# Uno_Hat.net
KiCad netlist of a schematic drawn in EasyEDA
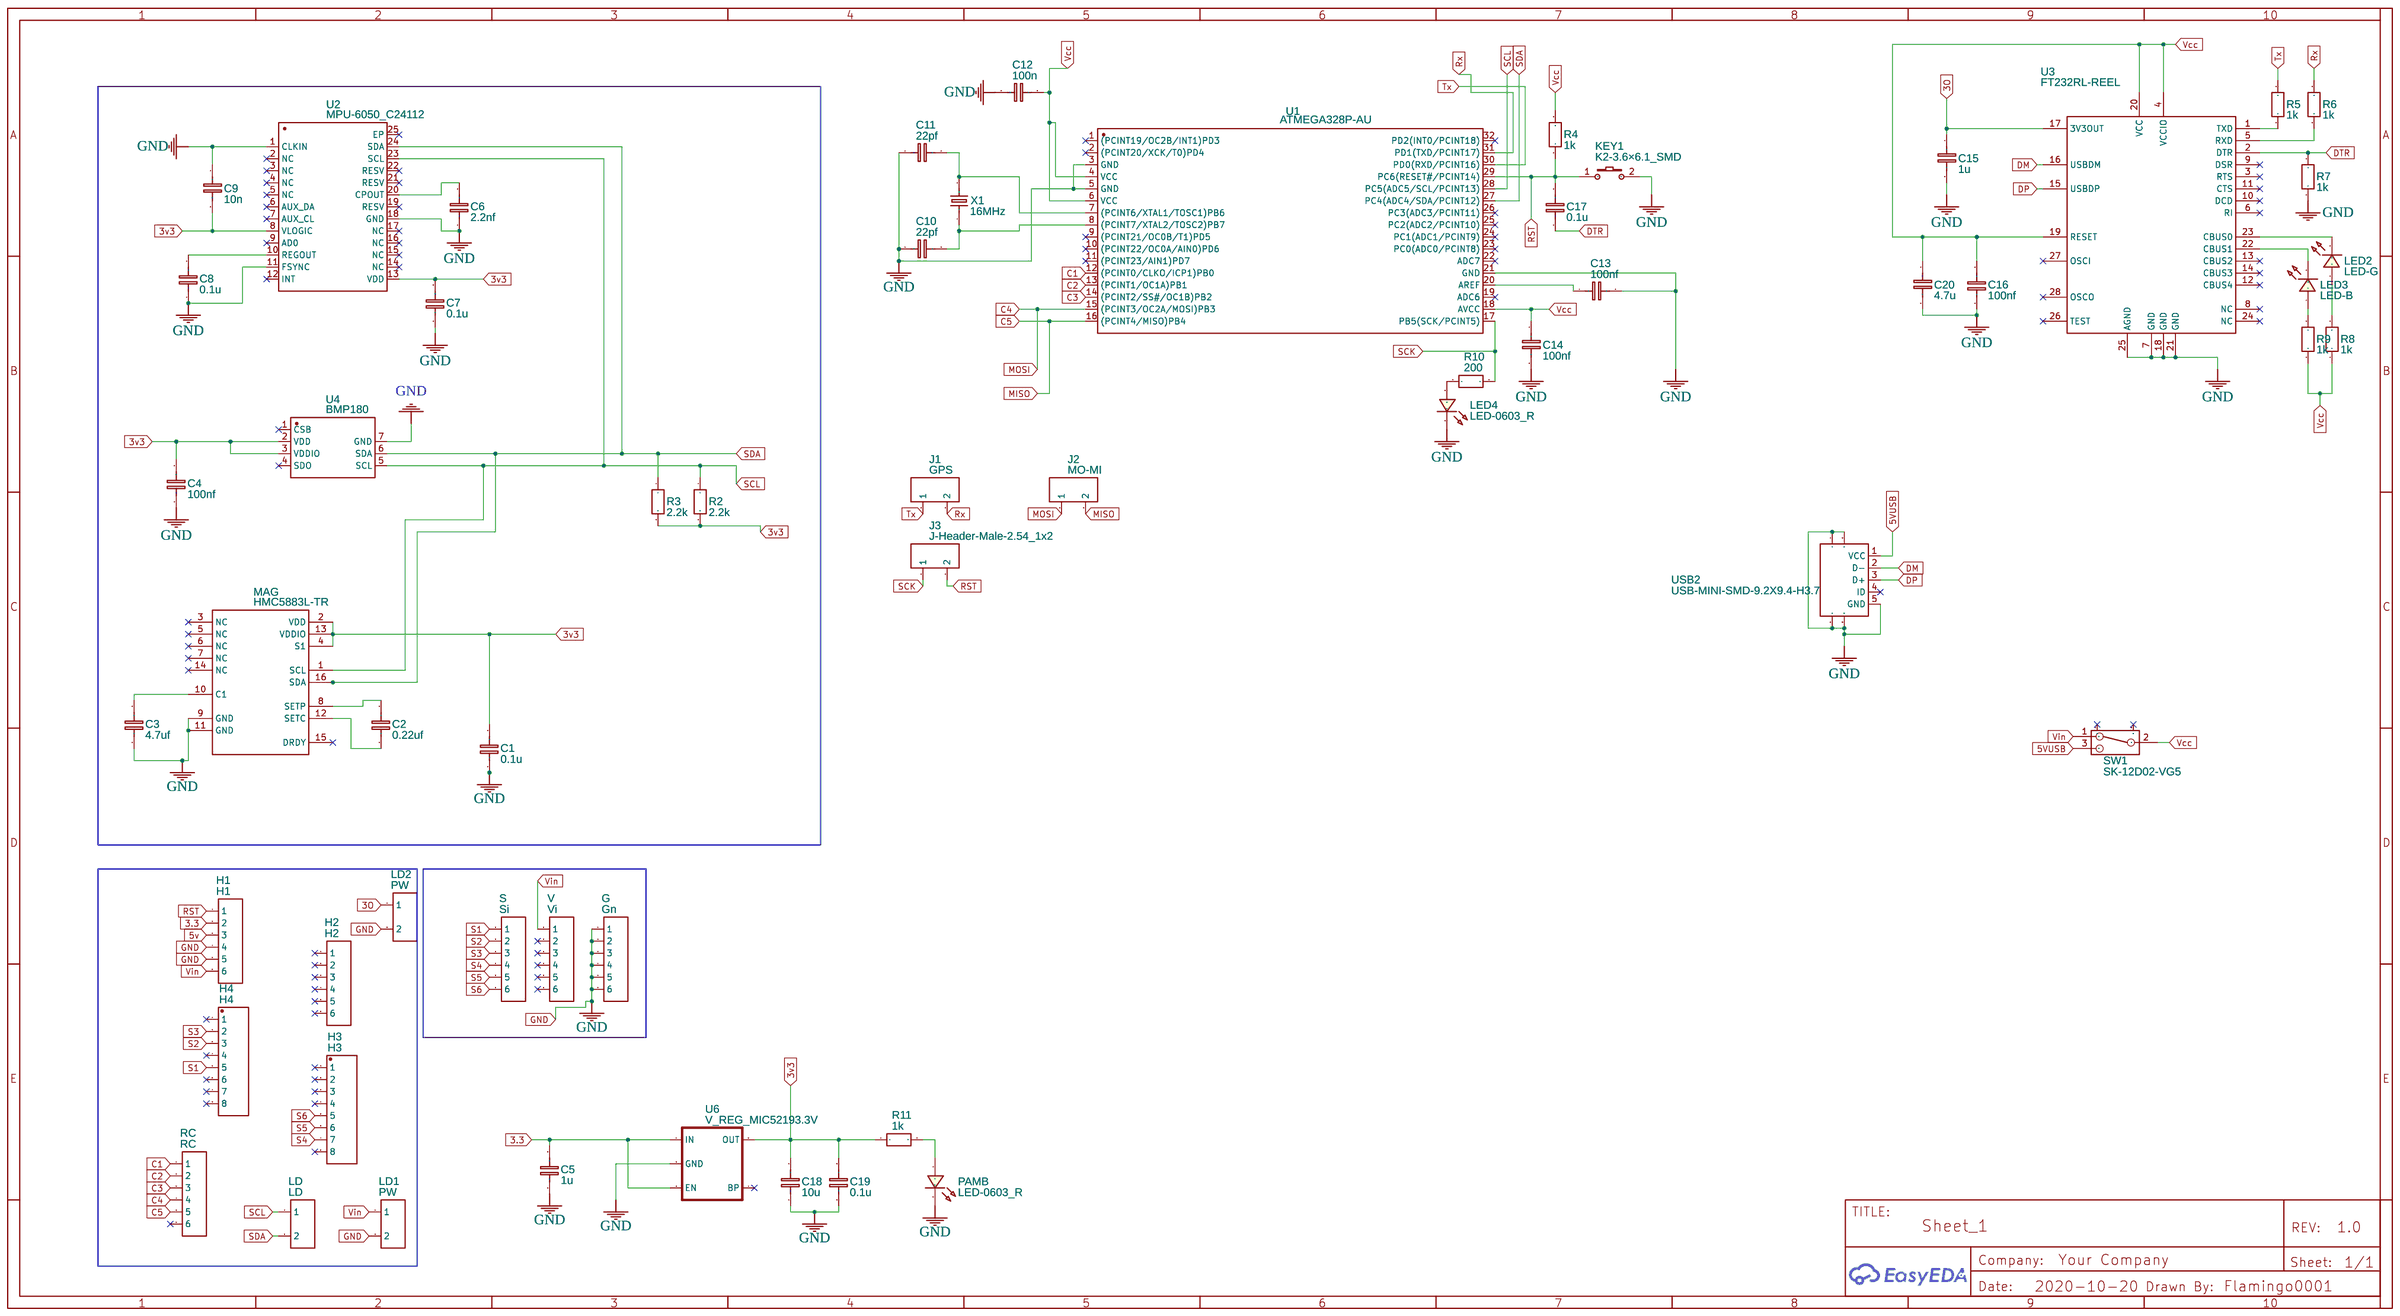
[diagram p0: schematic sheet]

(export (version "E")
  (design (tool "Eeschema 10.0.6"))
  (components
    (comp (ref "C1") (value "0.1u") (libsource (lib "") (part "C_0603_EU_3")))
    (comp (ref "C2") (value "0.22uf") (libsource (lib "") (part "C_0603_EU_3")))
    (comp (ref "C3") (value "4.7uf") (libsource (lib "") (part "C_0603_EU_4")))
    (comp (ref "C4") (value "100nf") (libsource (lib "") (part "C_0603_EU_4")))
    (comp (ref "C5") (value "1u") (libsource (lib "") (part "C_0603_EU_2")))
    (comp (ref "C6") (value "2.2nf") (libsource (lib "") (part "C_0603_EU_2")))
    (comp (ref "C7") (value "0.1u") (libsource (lib "") (part "C_0603_EU_2")))
    (comp (ref "C8") (value "0.1u") (libsource (lib "") (part "C_0603_EU")))
    (comp (ref "C9") (value "10n") (libsource (lib "") (part "C_0603_EU_1")))
    (comp (ref "C10") (value "22pf") (libsource (lib "") (part "C_0603_EU_5")))
    (comp (ref "C11") (value "22pf") (libsource (lib "") (part "C_0603_EU_5")))
    (comp (ref "C12") (value "100n") (libsource (lib "") (part "C_0603_EU_5")))
    (comp (ref "C13") (value "100nf") (libsource (lib "") (part "C_0603_EU_5")))
    (comp (ref "C14") (value "100nf") (libsource (lib "") (part "C_0603_EU_1")))
    (comp (ref "C15") (value "1u") (libsource (lib "") (part "C_0603_EU_1")))
    (comp (ref "C16") (value "100nf") (libsource (lib "") (part "C_0603_EU")))
    (comp (ref "C17") (value "0.1u") (libsource (lib "") (part "C_0603_EU")))
    (comp (ref "C18") (value "10u") (libsource (lib "") (part "C_0603_EU")))
    (comp (ref "C19") (value "0.1u") (libsource (lib "") (part "C_0603_EU")))
    (comp (ref "C20") (value "4.7u") (libsource (lib "") (part "C_0603_EU_1")))
    (comp (ref "G")
      (value "Gn")
      (fields
        (field (name "BOM_Manufacturer Part") "Header-Male-2.54_1x6")
        (field (name "BOM_Supplier Part") "C37208")
      )
      (libsource (lib "") (part "Header-Male-2.54_1x6_3"))
    )
    (comp (ref "H1")
      (value "H1")
      (fields
        (field (name "BOM_Manufacturer Part") "Header-Male-2.54_1x6")
        (field (name "BOM_Supplier Part") "C37208")
      )
      (libsource (lib "") (part "Header-Male-2.54_1x6_1"))
    )
    (comp (ref "H2")
      (value "H2")
      (fields
        (field (name "BOM_Manufacturer Part") "Header-Male-2.54_1x6")
        (field (name "BOM_Supplier Part") "C37208")
      )
      (libsource (lib "") (part "Header-Male-2.54_1x6_1"))
    )
    (comp (ref "H3")
      (value "H3")
      (fields
        (field (name "BOM_Manufacturer Part") "210S-1*8P L=11.6MMGold-plated black")
        (field (name "BOM_Supplier Part") "C124381")
      )
      (libsource (lib "") (part "Header-Male-2.54_1x8"))
    )
    (comp (ref "H4")
      (value "H4")
      (fields
        (field (name "BOM_Manufacturer Part") "210S-1*8P L=11.6MMGold-plated black")
        (field (name "BOM_Supplier Part") "C124381")
      )
      (libsource (lib "") (part "Header-Male-2.54_1x8"))
    )
    (comp (ref "J1")
      (value "GPS")
      (fields (field (name "BOM_Manufacturer Part") "826629-2") (field (name "BOM_Supplier Part") "C86471"))
      (libsource (lib "") (part "J-Header-Male-2.54_1x2"))
    )
    (comp (ref "J2")
      (value "MO-MI")
      (fields (field (name "BOM_Manufacturer Part") "826629-2") (field (name "BOM_Supplier Part") "C86471"))
      (libsource (lib "") (part "J-Header-Male-2.54_1x2"))
    )
    (comp (ref "J3")
      (value "J-Header-Male-2.54_1x2")
      (fields (field (name "BOM_Manufacturer Part") "826629-2") (field (name "BOM_Supplier Part") "C86471"))
      (libsource (lib "") (part "J-Header-Male-2.54_1x2"))
    )
    (comp (ref "KEY1")
      (value "K2-3.6×6.1_SMD")
      (fields
        (field (name "BOM_Manufacturer Part") "K2-1107ST-A4SW-06")
        (field (name "BOM_Supplier Part") "C118141")
      )
      (libsource (lib "") (part "K2-3.6×6.1_SMD"))
    )
    (comp (ref "LD")
      (value "LD")
      (fields (field (name "BOM_Manufacturer Part") "826629-2") (field (name "BOM_Supplier Part") "C86471"))
      (libsource (lib "") (part "Header-Male-2.54_1x2"))
    )
    (comp (ref "LD1")
      (value "PW")
      (fields (field (name "BOM_Manufacturer Part") "826629-2") (field (name "BOM_Supplier Part") "C86471"))
      (libsource (lib "") (part "Header-Male-2.54_1x2"))
    )
    (comp (ref "LD2")
      (value "PW")
      (fields (field (name "BOM_Manufacturer Part") "826629-2") (field (name "BOM_Supplier Part") "C86471"))
      (libsource (lib "") (part "Header-Male-2.54_1x2"))
    )
    (comp (ref "LED2")
      (value "LED-G")
      (fields
        (field (name "BOM_Manufacturer Part") "19-217/GHC-YR1S2/3T")
        (field (name "BOM_Supplier Part") "C72043")
      )
      (libsource (lib "") (part "LED-0603_G"))
    )
    (comp (ref "LED3")
      (value "LED-B")
      (fields
        (field (name "BOM_Manufacturer Part") "19-217/BHC-ZL1M2RY/3T")
        (field (name "BOM_Supplier Part") "C72041")
      )
      (libsource (lib "") (part "LED-0603_B"))
    )
    (comp (ref "LED4")
      (value "LED-0603_R")
      (fields
        (field (name "BOM_Manufacturer Part") "19-217/R6C-AL1M2VY/3T")
        (field (name "BOM_Supplier Part") "C72044")
      )
      (libsource (lib "") (part "LED-0603_R_1"))
    )
    (comp (ref "MAG")
      (value "HMC5883L-TR")
      (fields (field (name "BOM_Supplier Part") "C15640"))
      (libsource (lib "") (part "HMC5883L-TR"))
    )
    (comp (ref "PAMB")
      (value "LED-0603_R")
      (fields
        (field (name "BOM_Manufacturer Part") "19-217/R6C-AL1M2VY/3T")
        (field (name "BOM_Supplier Part") "C72044")
      )
      (libsource (lib "") (part "LED-0603_R"))
    )
    (comp (ref "R2") (value "2.2k") (libsource (lib "") (part "R_0603_EU_2")))
    (comp (ref "R3") (value "2.2k") (libsource (lib "") (part "R_0603_EU_2")))
    (comp (ref "R4") (value "1k") (libsource (lib "") (part "R_0603_EU_1")))
    (comp (ref "R5") (value "1k") (libsource (lib "") (part "R_0603_EU_1")))
    (comp (ref "R6") (value "1k") (libsource (lib "") (part "R_0603_EU_1")))
    (comp (ref "R7") (value "1k") (libsource (lib "") (part "R_0603_EU_1")))
    (comp (ref "R8") (value "1k") (libsource (lib "") (part "R_0603_EU_1")))
    (comp (ref "R9") (value "1k") (libsource (lib "") (part "R_0603_EU_1")))
    (comp (ref "R10") (value "200") (libsource (lib "") (part "R_0603_EU")))
    (comp (ref "R11") (value "1k") (libsource (lib "") (part "R_0603_EU")))
    (comp (ref "RC")
      (value "RC")
      (fields
        (field (name "BOM_Manufacturer Part") "Header-Male-2.54_1x6")
        (field (name "BOM_Supplier Part") "C37208")
      )
      (libsource (lib "") (part "Header-Male-2.54_1x6_4"))
    )
    (comp (ref "S")
      (value "Si")
      (fields
        (field (name "BOM_Manufacturer Part") "Header-Male-2.54_1x6")
        (field (name "BOM_Supplier Part") "C37208")
      )
      (libsource (lib "") (part "Header-Male-2.54_1x6_2"))
    )
    (comp (ref "SW1")
      (value "SK-12D02-VG5")
      (fields (field (name "BOM_Supplier Part") "C136722"))
      (libsource (lib "") (part "SK-12D02-VG5"))
    )
    (comp (ref "U1")
      (value "ATMEGA328P-AU")
      (fields (field (name "BOM_Supplier Part") "C14877"))
      (libsource (lib "") (part "ATMEGA328P-AU"))
    )
    (comp (ref "U2")
      (value "MPU-6050_C24112")
      (fields (field (name "BOM_Manufacturer Part") "MPU-6050") (field (name "BOM_Supplier Part") "C24112"))
      (libsource (lib "") (part "MPU-6050_C24112"))
    )
    (comp (ref "U3")
      (value "FT232RL-REEL")
      (fields (field (name "BOM_Supplier Part") "C8690"))
      (libsource (lib "") (part "FT232RL-REEL"))
    )
    (comp (ref "U4")
      (value "BMP180")
      (fields (field (name "BOM_Supplier Part") "C438474"))
      (libsource (lib "") (part "BMP180"))
    )
    (comp (ref "U6") (value "V_REG_MIC52193.3V") (libsource (lib "") (part "V_REG_MIC52193.3V")))
    (comp (ref "USB2")
      (value "USB-MINI-SMD-9.2X9.4-H3.7")
      (fields (field (name "BOM_Supplier Part") "C105424"))
      (libsource (lib "") (part "USB-MINI-SMD-9.2X9.4-H3.7"))
    )
    (comp (ref "V")
      (value "Vi")
      (fields
        (field (name "BOM_Manufacturer Part") "Header-Male-2.54_1x6")
        (field (name "BOM_Supplier Part") "C37208")
      )
      (libsource (lib "") (part "Header-Male-2.54_1x6"))
    )
    (comp (ref "X1")
      (value "16MHz")
      (fields
        (field (name "BOM_Manufacturer Part") "XIHCELNANF-16MHZ")
        (field (name "BOM_Supplier Part") "C295075")
      )
      (libsource (lib "") (part "XIHCELNANF-16MHZ"))
    )
  )
  (nets
    (net (code "1") (name "3.3") (class "Default")
      (node (ref "C5") (pin "2") (pinfunction "2_2") (pintype "unspecified"))
      (node (ref "H1") (pin "2") (pinfunction "2_2") (pintype "input"))
      (node (ref "U6") (pin "1") (pinfunction "IN_1") (pintype "input"))
      (node (ref "U6") (pin "3") (pinfunction "EN_3") (pintype "input"))
    )
    (net (code "2") (name "3O") (class "Default")
      (node (ref "C15") (pin "1") (pinfunction "1_1") (pintype "unspecified"))
      (node (ref "LD2") (pin "1") (pinfunction "1_1") (pintype "unspecified"))
      (node (ref "U3") (pin "17") (pinfunction "3V3OUT_17") (pintype "output"))
    )
    (net (code "3") (name "3v3") (class "Default")
      (node (ref "C1") (pin "2") (pinfunction "2_2") (pintype "unspecified"))
      (node (ref "C18") (pin "2") (pinfunction "2_2") (pintype "unspecified"))
      (node (ref "C19") (pin "2") (pinfunction "2_2") (pintype "unspecified"))
      (node (ref "C4") (pin "2") (pinfunction "2_2") (pintype "unspecified"))
      (node (ref "C7") (pin "2") (pinfunction "2_2") (pintype "unspecified"))
      (node (ref "C9") (pin "2") (pinfunction "2_2") (pintype "unspecified"))
      (node (ref "MAG") (pin "13") (pinfunction "VDDIO_13") (pintype "unspecified"))
      (node (ref "MAG") (pin "2") (pinfunction "VDD_2") (pintype "unspecified"))
      (node (ref "MAG") (pin "4") (pinfunction "S1_4") (pintype "unspecified"))
      (node (ref "R11") (pin "1") (pinfunction "1_1") (pintype "unspecified"))
      (node (ref "R2") (pin "2") (pinfunction "2_2") (pintype "unspecified"))
      (node (ref "R3") (pin "2") (pinfunction "2_2") (pintype "unspecified"))
      (node (ref "U2") (pin "13") (pinfunction "VDD_13") (pintype "unspecified"))
      (node (ref "U2") (pin "8") (pinfunction "VLOGIC_8") (pintype "unspecified"))
      (node (ref "U4") (pin "2") (pinfunction "VDD_2") (pintype "unspecified"))
      (node (ref "U4") (pin "3") (pinfunction "VDDIO_3") (pintype "unspecified"))
      (node (ref "U6") (pin "5") (pinfunction "OUT_5") (pintype "unspecified"))
    )
    (net (code "4") (name "5VUSB") (class "Default")
      (node (ref "SW1") (pin "3") (pinfunction "3_3") (pintype "unspecified"))
      (node (ref "USB2") (pin "1") (pinfunction "VCC_1") (pintype "input"))
    )
    (net (code "5") (name "5v") (class "Default")
      (node (ref "H1") (pin "3") (pinfunction "3_3") (pintype "input"))
    )
    (net (code "6") (name "C1") (class "Default")
      (node (ref "RC") (pin "1") (pinfunction "1_1") (pintype "input"))
      (node (ref "U1") (pin "12") (pinfunction "(PCINT0/CLKO/ICP1)PB0_12") (pintype "unspecified"))
    )
    (net (code "7") (name "C2") (class "Default")
      (node (ref "RC") (pin "2") (pinfunction "2_2") (pintype "input"))
      (node (ref "U1") (pin "13") (pinfunction "(PCINT1/OC1A)PB1_13") (pintype "unspecified"))
    )
    (net (code "8") (name "C3") (class "Default")
      (node (ref "RC") (pin "3") (pinfunction "3_3") (pintype "input"))
      (node (ref "U1") (pin "14") (pinfunction "(PCINT2/SS#/OC1B)PB2_14") (pintype "unspecified"))
    )
    (net (code "9") (name "C4") (class "Default")
      (node (ref "J2") (pin "1") (pinfunction "1_1") (pintype "unspecified"))
      (node (ref "RC") (pin "4") (pinfunction "4_4") (pintype "input"))
      (node (ref "U1") (pin "15") (pinfunction "(PCINT3/OC2A/MOSI)PB3_15") (pintype "unspecified"))
    )
    (net (code "10") (name "C5") (class "Default")
      (node (ref "J2") (pin "2") (pinfunction "2_2") (pintype "unspecified"))
      (node (ref "RC") (pin "5") (pinfunction "5_5") (pintype "input"))
      (node (ref "U1") (pin "16") (pinfunction "(PCINT4/MISO)PB4_16") (pintype "unspecified"))
    )
    (net (code "11") (name "DM") (class "Default")
      (node (ref "U3") (pin "16") (pinfunction "USBDM_16") (pintype "bidirectional"))
      (node (ref "USB2") (pin "2") (pinfunction "D-_2") (pintype "input"))
    )
    (net (code "12") (name "DP") (class "Default")
      (node (ref "U3") (pin "15") (pinfunction "USBDP_15") (pintype "bidirectional"))
      (node (ref "USB2") (pin "3") (pinfunction "D+_3") (pintype "input"))
    )
    (net (code "13") (name "DTR") (class "Default")
      (node (ref "C17") (pin "1") (pinfunction "1_1") (pintype "unspecified"))
      (node (ref "R7") (pin "2") (pinfunction "2_2") (pintype "unspecified"))
      (node (ref "U3") (pin "2") (pinfunction "DTR_2") (pintype "output"))
    )
    (net (code "14") (name "GND") (class "Default")
      (node (ref "C1") (pin "1") (pinfunction "1_1") (pintype "unspecified"))
      (node (ref "C10") (pin "1") (pinfunction "1_1") (pintype "unspecified"))
      (node (ref "C11") (pin "1") (pinfunction "1_1") (pintype "unspecified"))
      (node (ref "C12") (pin "1") (pinfunction "1_1") (pintype "unspecified"))
      (node (ref "C13") (pin "2") (pinfunction "2_2") (pintype "unspecified"))
      (node (ref "C14") (pin "2") (pinfunction "2_2") (pintype "unspecified"))
      (node (ref "C15") (pin "2") (pinfunction "2_2") (pintype "unspecified"))
      (node (ref "C16") (pin "1") (pinfunction "1_1") (pintype "unspecified"))
      (node (ref "C18") (pin "1") (pinfunction "1_1") (pintype "unspecified"))
      (node (ref "C19") (pin "1") (pinfunction "1_1") (pintype "unspecified"))
      (node (ref "C20") (pin "2") (pinfunction "2_2") (pintype "unspecified"))
      (node (ref "C3") (pin "1") (pinfunction "1_1") (pintype "unspecified"))
      (node (ref "C4") (pin "1") (pinfunction "1_1") (pintype "unspecified"))
      (node (ref "C5") (pin "1") (pinfunction "1_1") (pintype "unspecified"))
      (node (ref "C6") (pin "1") (pinfunction "1_1") (pintype "unspecified"))
      (node (ref "C7") (pin "1") (pinfunction "1_1") (pintype "unspecified"))
      (node (ref "C8") (pin "1") (pinfunction "1_1") (pintype "unspecified"))
      (node (ref "C9") (pin "1") (pinfunction "1_1") (pintype "unspecified"))
      (node (ref "G") (pin "1") (pinfunction "1_1") (pintype "input"))
      (node (ref "G") (pin "2") (pinfunction "2_2") (pintype "input"))
      (node (ref "G") (pin "3") (pinfunction "3_3") (pintype "input"))
      (node (ref "G") (pin "4") (pinfunction "4_4") (pintype "input"))
      (node (ref "G") (pin "5") (pinfunction "5_5") (pintype "input"))
      (node (ref "G") (pin "6") (pinfunction "6_6") (pintype "input"))
      (node (ref "H1") (pin "4") (pinfunction "4_4") (pintype "input"))
      (node (ref "H1") (pin "5") (pinfunction "5_5") (pintype "input"))
      (node (ref "KEY1") (pin "2") (pinfunction "2_2") (pintype "unspecified"))
      (node (ref "LD1") (pin "2") (pinfunction "2_2") (pintype "unspecified"))
      (node (ref "LD2") (pin "2") (pinfunction "2_2") (pintype "unspecified"))
      (node (ref "LED4") (pin "2") (pinfunction "2_2") (pintype "unspecified"))
      (node (ref "MAG") (pin "11") (pinfunction "GND_11") (pintype "unspecified"))
      (node (ref "MAG") (pin "9") (pinfunction "GND_9") (pintype "unspecified"))
      (node (ref "PAMB") (pin "2") (pinfunction "2_2") (pintype "unspecified"))
      (node (ref "R7") (pin "1") (pinfunction "1_1") (pintype "unspecified"))
      (node (ref "U1") (pin "21") (pinfunction "GND_21") (pintype "unspecified"))
      (node (ref "U1") (pin "3") (pinfunction "GND_3") (pintype "unspecified"))
      (node (ref "U1") (pin "5") (pinfunction "GND_5") (pintype "unspecified"))
      (node (ref "U2") (pin "1") (pinfunction "CLKIN_1") (pintype "unspecified"))
      (node (ref "U2") (pin "11") (pinfunction "FSYNC_11") (pintype "unspecified"))
      (node (ref "U2") (pin "18") (pinfunction "GND_18") (pintype "unspecified"))
      (node (ref "U3") (pin "18") (pinfunction "GND_18") (pintype "passive"))
      (node (ref "U3") (pin "21") (pinfunction "GND_21") (pintype "passive"))
      (node (ref "U3") (pin "25") (pinfunction "AGND_25") (pintype "passive"))
      (node (ref "U3") (pin "7") (pinfunction "GND_7") (pintype "passive"))
      (node (ref "U4") (pin "7") (pinfunction "GND_7") (pintype "unspecified"))
      (node (ref "U6") (pin "2") (pinfunction "GND_2") (pintype "input"))
      (node (ref "USB2") (pin "5") (pinfunction "GND_5") (pintype "input"))
      (node (ref "USB2") (pin "6") (pinfunction "6_6") (pintype "unspecified"))
      (node (ref "USB2") (pin "7") (pinfunction "7_7") (pintype "unspecified"))
      (node (ref "USB2") (pin "8") (pinfunction "8_8") (pintype "unspecified"))
      (node (ref "USB2") (pin "9") (pinfunction "9_9") (pintype "unspecified"))
    )
    (net (code "15") (name "Net-(LED2-Pad1)") (class "Default")
      (node (ref "LED2") (pin "1") (pinfunction "1_1") (pintype "unspecified"))
      (node (ref "R8") (pin "2") (pinfunction "2_2") (pintype "unspecified"))
    )
    (net (code "16") (name "Net-(LED3-Pad1)") (class "Default")
      (node (ref "LED3") (pin "1") (pinfunction "1_1") (pintype "unspecified"))
      (node (ref "R9") (pin "2") (pinfunction "2_2") (pintype "unspecified"))
    )
    (net (code "17") (name "Net-(LED4-Pad1)") (class "Default")
      (node (ref "LED4") (pin "1") (pinfunction "1_1") (pintype "unspecified"))
      (node (ref "R10") (pin "1") (pinfunction "1_1") (pintype "unspecified"))
    )
    (net (code "18") (name "Net-(MAG-C1)") (class "Default")
      (node (ref "C3") (pin "2") (pinfunction "2_2") (pintype "unspecified"))
      (node (ref "MAG") (pin "10") (pinfunction "C1_10") (pintype "unspecified"))
    )
    (net (code "19") (name "Net-(MAG-SETC)") (class "Default")
      (node (ref "C2") (pin "1") (pinfunction "1_1") (pintype "unspecified"))
      (node (ref "MAG") (pin "12") (pinfunction "SETC_12") (pintype "unspecified"))
    )
    (net (code "20") (name "Net-(MAG-SETP)") (class "Default")
      (node (ref "C2") (pin "2") (pinfunction "2_2") (pintype "unspecified"))
      (node (ref "MAG") (pin "8") (pinfunction "SETP_8") (pintype "unspecified"))
    )
    (net (code "21") (name "Net-(PAMB-Pad1)") (class "Default")
      (node (ref "PAMB") (pin "1") (pinfunction "1_1") (pintype "unspecified"))
      (node (ref "R11") (pin "2") (pinfunction "2_2") (pintype "unspecified"))
    )
    (net (code "22") (name "Net-(U1-(PCINT6{slash}XTAL1{slash}TOSC1)PB6)") (class "Default")
      (node (ref "C11") (pin "2") (pinfunction "2_2") (pintype "unspecified"))
      (node (ref "U1") (pin "7") (pinfunction "(PCINT6/XTAL1/TOSC1)PB6_7") (pintype "unspecified"))
      (node (ref "X1") (pin "2") (pinfunction "2_2") (pintype "unspecified"))
    )
    (net (code "23") (name "Net-(U1-(PCINT7{slash}XTAL2{slash}TOSC2)PB7)") (class "Default")
      (node (ref "C10") (pin "2") (pinfunction "2_2") (pintype "unspecified"))
      (node (ref "U1") (pin "8") (pinfunction "(PCINT7/XTAL2/TOSC2)PB7_8") (pintype "unspecified"))
      (node (ref "X1") (pin "1") (pinfunction "1_1") (pintype "unspecified"))
    )
    (net (code "24") (name "Net-(U1-AREF)") (class "Default")
      (node (ref "C13") (pin "1") (pinfunction "1_1") (pintype "unspecified"))
      (node (ref "U1") (pin "20") (pinfunction "AREF_20") (pintype "unspecified"))
    )
    (net (code "25") (name "Net-(U2-CPOUT)") (class "Default")
      (node (ref "C6") (pin "2") (pinfunction "2_2") (pintype "unspecified"))
      (node (ref "U2") (pin "20") (pinfunction "CPOUT_20") (pintype "unspecified"))
    )
    (net (code "26") (name "Net-(U2-REGOUT)") (class "Default")
      (node (ref "C8") (pin "2") (pinfunction "2_2") (pintype "unspecified"))
      (node (ref "U2") (pin "10") (pinfunction "REGOUT_10") (pintype "unspecified"))
    )
    (net (code "27") (name "Net-(U3-CBUS0)") (class "Default")
      (node (ref "LED2") (pin "2") (pinfunction "2_2") (pintype "unspecified"))
      (node (ref "U3") (pin "23") (pinfunction "CBUS0_23") (pintype "bidirectional"))
    )
    (net (code "28") (name "Net-(U3-CBUS1)") (class "Default")
      (node (ref "LED3") (pin "2") (pinfunction "2_2") (pintype "unspecified"))
      (node (ref "U3") (pin "22") (pinfunction "CBUS1_22") (pintype "bidirectional"))
    )
    (net (code "29") (name "Net-(U3-RXD)") (class "Default")
      (node (ref "R6") (pin "1") (pinfunction "1_1") (pintype "unspecified"))
      (node (ref "U3") (pin "5") (pinfunction "RXD_5") (pintype "unspecified"))
    )
    (net (code "30") (name "Net-(U3-TXD)") (class "Default")
      (node (ref "R5") (pin "1") (pinfunction "1_1") (pintype "unspecified"))
      (node (ref "U3") (pin "1") (pinfunction "TXD_1") (pintype "output"))
    )
    (net (code "31") (name "RST") (class "Default")
      (node (ref "C17") (pin "2") (pinfunction "2_2") (pintype "unspecified"))
      (node (ref "H1") (pin "1") (pinfunction "1_1") (pintype "input"))
      (node (ref "J3") (pin "2") (pinfunction "2_2") (pintype "unspecified"))
      (node (ref "KEY1") (pin "1") (pinfunction "1_1") (pintype "unspecified"))
      (node (ref "R4") (pin "1") (pinfunction "1_1") (pintype "unspecified"))
      (node (ref "U1") (pin "29") (pinfunction "PC6(RESET#/PCINT14)_29") (pintype "unspecified"))
    )
    (net (code "32") (name "Rx") (class "Default")
      (node (ref "J1") (pin "2") (pinfunction "2_2") (pintype "unspecified"))
      (node (ref "R6") (pin "2") (pinfunction "2_2") (pintype "unspecified"))
      (node (ref "U1") (pin "31") (pinfunction "PD1(TXD/PCINT17)_31") (pintype "unspecified"))
    )
    (net (code "33") (name "S1") (class "Default")
      (node (ref "H4") (pin "5") (pinfunction "5_5") (pintype "unspecified"))
      (node (ref "S") (pin "1") (pinfunction "1_1") (pintype "input"))
    )
    (net (code "34") (name "S2") (class "Default")
      (node (ref "H4") (pin "3") (pinfunction "3_3") (pintype "unspecified"))
      (node (ref "S") (pin "2") (pinfunction "2_2") (pintype "input"))
    )
    (net (code "35") (name "S3") (class "Default")
      (node (ref "H4") (pin "2") (pinfunction "2_2") (pintype "unspecified"))
      (node (ref "S") (pin "3") (pinfunction "3_3") (pintype "input"))
    )
    (net (code "36") (name "S4") (class "Default")
      (node (ref "H3") (pin "7") (pinfunction "7_7") (pintype "unspecified"))
      (node (ref "S") (pin "4") (pinfunction "4_4") (pintype "input"))
    )
    (net (code "37") (name "S5") (class "Default")
      (node (ref "H3") (pin "6") (pinfunction "6_6") (pintype "unspecified"))
      (node (ref "S") (pin "5") (pinfunction "5_5") (pintype "input"))
    )
    (net (code "38") (name "S6") (class "Default")
      (node (ref "H3") (pin "5") (pinfunction "5_5") (pintype "unspecified"))
      (node (ref "S") (pin "6") (pinfunction "6_6") (pintype "input"))
    )
    (net (code "39") (name "SCK") (class "Default")
      (node (ref "J3") (pin "1") (pinfunction "1_1") (pintype "unspecified"))
      (node (ref "R10") (pin "2") (pinfunction "2_2") (pintype "unspecified"))
      (node (ref "U1") (pin "17") (pinfunction "PB5(SCK/PCINT5)_17") (pintype "unspecified"))
    )
    (net (code "40") (name "SCL") (class "Default")
      (node (ref "LD") (pin "1") (pinfunction "1_1") (pintype "unspecified"))
      (node (ref "MAG") (pin "1") (pinfunction "SCL_1") (pintype "unspecified"))
      (node (ref "R2") (pin "1") (pinfunction "1_1") (pintype "unspecified"))
      (node (ref "U1") (pin "28") (pinfunction "PC5(ADC5/SCL/PCINT13)_28") (pintype "unspecified"))
      (node (ref "U2") (pin "23") (pinfunction "SCL_23") (pintype "unspecified"))
      (node (ref "U4") (pin "5") (pinfunction "SCL_5") (pintype "unspecified"))
    )
    (net (code "41") (name "SDA") (class "Default")
      (node (ref "LD") (pin "2") (pinfunction "2_2") (pintype "unspecified"))
      (node (ref "MAG") (pin "16") (pinfunction "SDA_16") (pintype "unspecified"))
      (node (ref "R3") (pin "1") (pinfunction "1_1") (pintype "unspecified"))
      (node (ref "U1") (pin "27") (pinfunction "PC4(ADC4/SDA/PCINT12)_27") (pintype "unspecified"))
      (node (ref "U2") (pin "24") (pinfunction "SDA_24") (pintype "unspecified"))
      (node (ref "U4") (pin "6") (pinfunction "SDA_6") (pintype "unspecified"))
    )
    (net (code "42") (name "Tx") (class "Default")
      (node (ref "J1") (pin "1") (pinfunction "1_1") (pintype "unspecified"))
      (node (ref "R5") (pin "2") (pinfunction "2_2") (pintype "unspecified"))
      (node (ref "U1") (pin "30") (pinfunction "PD0(RXD/PCINT16)_30") (pintype "unspecified"))
    )
    (net (code "43") (name "Vcc") (class "Default")
      (node (ref "C12") (pin "2") (pinfunction "2_2") (pintype "unspecified"))
      (node (ref "C14") (pin "1") (pinfunction "1_1") (pintype "unspecified"))
      (node (ref "C16") (pin "2") (pinfunction "2_2") (pintype "unspecified"))
      (node (ref "C20") (pin "1") (pinfunction "1_1") (pintype "unspecified"))
      (node (ref "R4") (pin "2") (pinfunction "2_2") (pintype "unspecified"))
      (node (ref "R8") (pin "1") (pinfunction "1_1") (pintype "unspecified"))
      (node (ref "R9") (pin "1") (pinfunction "1_1") (pintype "unspecified"))
      (node (ref "SW1") (pin "2") (pinfunction "2_2") (pintype "unspecified"))
      (node (ref "U1") (pin "18") (pinfunction "AVCC_18") (pintype "unspecified"))
      (node (ref "U1") (pin "4") (pinfunction "VCC_4") (pintype "unspecified"))
      (node (ref "U1") (pin "6") (pinfunction "VCC_6") (pintype "unspecified"))
      (node (ref "U3") (pin "19") (pinfunction "RESET_19") (pintype "unspecified"))
      (node (ref "U3") (pin "20") (pinfunction "VCC_20") (pintype "passive"))
      (node (ref "U3") (pin "4") (pinfunction "VCCIO_4") (pintype "passive"))
    )
    (net (code "44") (name "Vin") (class "Default")
      (node (ref "H1") (pin "6") (pinfunction "6_6") (pintype "input"))
      (node (ref "LD1") (pin "1") (pinfunction "1_1") (pintype "unspecified"))
      (node (ref "SW1") (pin "1") (pinfunction "1_1") (pintype "unspecified"))
      (node (ref "V") (pin "1") (pinfunction "1_1") (pintype "input"))
    )
    (net (code "45") (name "unconnected-(H2-Pad1)") (class "Default")
      (node (ref "H2") (pin "1") (pinfunction "1_1") (pintype "input+no_connect"))
    )
    (net (code "46") (name "unconnected-(H2-Pad2)") (class "Default")
      (node (ref "H2") (pin "2") (pinfunction "2_2") (pintype "input+no_connect"))
    )
    (net (code "47") (name "unconnected-(H2-Pad3)") (class "Default")
      (node (ref "H2") (pin "3") (pinfunction "3_3") (pintype "input+no_connect"))
    )
    (net (code "48") (name "unconnected-(H2-Pad4)") (class "Default")
      (node (ref "H2") (pin "4") (pinfunction "4_4") (pintype "input+no_connect"))
    )
    (net (code "49") (name "unconnected-(H2-Pad5)") (class "Default")
      (node (ref "H2") (pin "5") (pinfunction "5_5") (pintype "input+no_connect"))
    )
    (net (code "50") (name "unconnected-(H2-Pad6)") (class "Default")
      (node (ref "H2") (pin "6") (pinfunction "6_6") (pintype "input+no_connect"))
    )
    (net (code "51") (name "unconnected-(H3-Pad1)") (class "Default")
      (node (ref "H3") (pin "1") (pinfunction "1_1") (pintype "unspecified+no_connect"))
    )
    (net (code "52") (name "unconnected-(H3-Pad2)") (class "Default")
      (node (ref "H3") (pin "2") (pinfunction "2_2") (pintype "unspecified+no_connect"))
    )
    (net (code "53") (name "unconnected-(H3-Pad3)") (class "Default")
      (node (ref "H3") (pin "3") (pinfunction "3_3") (pintype "unspecified+no_connect"))
    )
    (net (code "54") (name "unconnected-(H3-Pad4)") (class "Default")
      (node (ref "H3") (pin "4") (pinfunction "4_4") (pintype "unspecified+no_connect"))
    )
    (net (code "55") (name "unconnected-(H3-Pad8)") (class "Default")
      (node (ref "H3") (pin "8") (pinfunction "8_8") (pintype "unspecified+no_connect"))
    )
    (net (code "56") (name "unconnected-(H4-Pad1)") (class "Default")
      (node (ref "H4") (pin "1") (pinfunction "1_1") (pintype "unspecified+no_connect"))
    )
    (net (code "57") (name "unconnected-(H4-Pad4)") (class "Default")
      (node (ref "H4") (pin "4") (pinfunction "4_4") (pintype "unspecified+no_connect"))
    )
    (net (code "58") (name "unconnected-(H4-Pad6)") (class "Default")
      (node (ref "H4") (pin "6") (pinfunction "6_6") (pintype "unspecified+no_connect"))
    )
    (net (code "59") (name "unconnected-(H4-Pad7)") (class "Default")
      (node (ref "H4") (pin "7") (pinfunction "7_7") (pintype "unspecified+no_connect"))
    )
    (net (code "60") (name "unconnected-(H4-Pad8)") (class "Default")
      (node (ref "H4") (pin "8") (pinfunction "8_8") (pintype "unspecified+no_connect"))
    )
    (net (code "61") (name "unconnected-(MAG-DRDY-Pad15)") (class "Default")
      (node (ref "MAG") (pin "15") (pinfunction "DRDY_15") (pintype "unspecified+no_connect"))
    )
    (net (code "62") (name "unconnected-(MAG-NC-Pad3)") (class "Default")
      (node (ref "MAG") (pin "3") (pinfunction "NC_3") (pintype "unspecified+no_connect"))
    )
    (net (code "63") (name "unconnected-(MAG-NC-Pad5)") (class "Default")
      (node (ref "MAG") (pin "5") (pinfunction "NC_5") (pintype "unspecified+no_connect"))
    )
    (net (code "64") (name "unconnected-(MAG-NC-Pad6)") (class "Default")
      (node (ref "MAG") (pin "6") (pinfunction "NC_6") (pintype "unspecified+no_connect"))
    )
    (net (code "65") (name "unconnected-(MAG-NC-Pad7)") (class "Default")
      (node (ref "MAG") (pin "7") (pinfunction "NC_7") (pintype "unspecified+no_connect"))
    )
    (net (code "66") (name "unconnected-(MAG-NC-Pad14)") (class "Default")
      (node (ref "MAG") (pin "14") (pinfunction "NC_14") (pintype "unspecified+no_connect"))
    )
    (net (code "67") (name "unconnected-(RC-Pad6)") (class "Default")
      (node (ref "RC") (pin "6") (pinfunction "6_6") (pintype "input+no_connect"))
    )
    (net (code "68") (name "unconnected-(SW1-Pad4)") (class "Default")
      (node (ref "SW1") (pin "4") (pinfunction "4_4") (pintype "unspecified+no_connect"))
    )
    (net (code "69") (name "unconnected-(SW1-Pad5)") (class "Default")
      (node (ref "SW1") (pin "5") (pinfunction "5_5") (pintype "unspecified+no_connect"))
    )
    (net (code "70") (name "unconnected-(U1-(PCINT19{slash}OC2B{slash}INT1)PD3-Pad1)") (class "Default")
      (node (ref "U1") (pin "1") (pinfunction "(PCINT19/OC2B/INT1)PD3_1") (pintype "unspecified+no_connect"))
    )
    (net (code "71") (name "unconnected-(U1-(PCINT20{slash}XCK{slash}T0)PD4-Pad2)") (class "Default")
      (node (ref "U1") (pin "2") (pinfunction "(PCINT20/XCK/T0)PD4_2") (pintype "unspecified+no_connect"))
    )
    (net (code "72") (name "unconnected-(U1-(PCINT21{slash}OC0B{slash}T1)PD5-Pad9)") (class "Default")
      (node (ref "U1") (pin "9") (pinfunction "(PCINT21/OC0B/T1)PD5_9") (pintype "unspecified+no_connect"))
    )
    (net (code "73") (name "unconnected-(U1-(PCINT22{slash}OC0A{slash}AIN0)PD6-Pad10)") (class "Default")
      (node (ref "U1") (pin "10") (pinfunction "(PCINT22/OC0A/AIN0)PD6_10") (pintype "unspecified+no_connect"))
    )
    (net (code "74") (name "unconnected-(U1-(PCINT23{slash}AIN1)PD7-Pad11)") (class "Default")
      (node (ref "U1") (pin "11") (pinfunction "(PCINT23/AIN1)PD7_11") (pintype "unspecified+no_connect"))
    )
    (net (code "75") (name "unconnected-(U1-ADC6-Pad19)") (class "Default")
      (node (ref "U1") (pin "19") (pinfunction "ADC6_19") (pintype "unspecified+no_connect"))
    )
    (net (code "76") (name "unconnected-(U1-ADC7-Pad22)") (class "Default")
      (node (ref "U1") (pin "22") (pinfunction "ADC7_22") (pintype "unspecified+no_connect"))
    )
    (net (code "77") (name "unconnected-(U1-PC0(ADC0{slash}PCINT8)-Pad23)") (class "Default")
      (node (ref "U1") (pin "23") (pinfunction "PC0(ADC0/PCINT8)_23") (pintype "unspecified+no_connect"))
    )
    (net (code "78") (name "unconnected-(U1-PC1(ADC1{slash}PCINT9)-Pad24)") (class "Default")
      (node (ref "U1") (pin "24") (pinfunction "PC1(ADC1/PCINT9)_24") (pintype "unspecified+no_connect"))
    )
    (net (code "79") (name "unconnected-(U1-PC2(ADC2{slash}PCINT10)-Pad25)") (class "Default")
      (node (ref "U1") (pin "25") (pinfunction "PC2(ADC2/PCINT10)_25") (pintype "unspecified+no_connect"))
    )
    (net (code "80") (name "unconnected-(U1-PC3(ADC3{slash}PCINT11)-Pad26)") (class "Default")
      (node (ref "U1") (pin "26") (pinfunction "PC3(ADC3/PCINT11)_26") (pintype "unspecified+no_connect"))
    )
    (net (code "81") (name "unconnected-(U1-PD2(INT0{slash}PCINT18)-Pad32)") (class "Default")
      (node (ref "U1") (pin "32") (pinfunction "PD2(INT0/PCINT18)_32") (pintype "unspecified+no_connect"))
    )
    (net (code "82") (name "unconnected-(U2-AD0-Pad9)") (class "Default")
      (node (ref "U2") (pin "9") (pinfunction "AD0_9") (pintype "unspecified+no_connect"))
    )
    (net (code "83") (name "unconnected-(U2-AUX_CL-Pad7)") (class "Default")
      (node (ref "U2") (pin "7") (pinfunction "AUX_CL_7") (pintype "unspecified+no_connect"))
    )
    (net (code "84") (name "unconnected-(U2-AUX_DA-Pad6)") (class "Default")
      (node (ref "U2") (pin "6") (pinfunction "AUX_DA_6") (pintype "unspecified+no_connect"))
    )
    (net (code "85") (name "unconnected-(U2-EP-Pad25)") (class "Default")
      (node (ref "U2") (pin "25") (pinfunction "EP_25") (pintype "unspecified+no_connect"))
    )
    (net (code "86") (name "unconnected-(U2-INT-Pad12)") (class "Default")
      (node (ref "U2") (pin "12") (pinfunction "INT_12") (pintype "unspecified+no_connect"))
    )
    (net (code "87") (name "unconnected-(U2-NC-Pad2)") (class "Default")
      (node (ref "U2") (pin "2") (pinfunction "NC_2") (pintype "unspecified+no_connect"))
    )
    (net (code "88") (name "unconnected-(U2-NC-Pad3)") (class "Default")
      (node (ref "U2") (pin "3") (pinfunction "NC_3") (pintype "unspecified+no_connect"))
    )
    (net (code "89") (name "unconnected-(U2-NC-Pad4)") (class "Default")
      (node (ref "U2") (pin "4") (pinfunction "NC_4") (pintype "unspecified+no_connect"))
    )
    (net (code "90") (name "unconnected-(U2-NC-Pad5)") (class "Default")
      (node (ref "U2") (pin "5") (pinfunction "NC_5") (pintype "unspecified+no_connect"))
    )
    (net (code "91") (name "unconnected-(U2-NC-Pad14)") (class "Default")
      (node (ref "U2") (pin "14") (pinfunction "NC_14") (pintype "unspecified+no_connect"))
    )
    (net (code "92") (name "unconnected-(U2-NC-Pad15)") (class "Default")
      (node (ref "U2") (pin "15") (pinfunction "NC_15") (pintype "unspecified+no_connect"))
    )
    (net (code "93") (name "unconnected-(U2-NC-Pad16)") (class "Default")
      (node (ref "U2") (pin "16") (pinfunction "NC_16") (pintype "unspecified+no_connect"))
    )
    (net (code "94") (name "unconnected-(U2-NC-Pad17)") (class "Default")
      (node (ref "U2") (pin "17") (pinfunction "NC_17") (pintype "unspecified+no_connect"))
    )
    (net (code "95") (name "unconnected-(U2-RESV-Pad19)") (class "Default")
      (node (ref "U2") (pin "19") (pinfunction "RESV_19") (pintype "unspecified+no_connect"))
    )
    (net (code "96") (name "unconnected-(U2-RESV-Pad21)") (class "Default")
      (node (ref "U2") (pin "21") (pinfunction "RESV_21") (pintype "unspecified+no_connect"))
    )
    (net (code "97") (name "unconnected-(U2-RESV-Pad22)") (class "Default")
      (node (ref "U2") (pin "22") (pinfunction "RESV_22") (pintype "unspecified+no_connect"))
    )
    (net (code "98") (name "unconnected-(U3-CBUS2-Pad13)") (class "Default")
      (node (ref "U3") (pin "13") (pinfunction "CBUS2_13") (pintype "bidirectional+no_connect"))
    )
    (net (code "99") (name "unconnected-(U3-CBUS3-Pad14)") (class "Default")
      (node (ref "U3") (pin "14") (pinfunction "CBUS3_14") (pintype "bidirectional+no_connect"))
    )
    (net (code "100") (name "unconnected-(U3-CBUS4-Pad12)") (class "Default")
      (node (ref "U3") (pin "12") (pinfunction "CBUS4_12") (pintype "bidirectional+no_connect"))
    )
    (net (code "101") (name "unconnected-(U3-CTS-Pad11)") (class "Default")
      (node (ref "U3") (pin "11") (pinfunction "CTS_11") (pintype "unspecified+no_connect"))
    )
    (net (code "102") (name "unconnected-(U3-DCD-Pad10)") (class "Default")
      (node (ref "U3") (pin "10") (pinfunction "DCD_10") (pintype "unspecified+no_connect"))
    )
    (net (code "103") (name "unconnected-(U3-DSR-Pad9)") (class "Default")
      (node (ref "U3") (pin "9") (pinfunction "DSR_9") (pintype "unspecified+no_connect"))
    )
    (net (code "104") (name "unconnected-(U3-NC-Pad8)") (class "Default")
      (node (ref "U3") (pin "8") (pinfunction "NC_8") (pintype "unspecified+no_connect"))
    )
    (net (code "105") (name "unconnected-(U3-NC-Pad24)") (class "Default")
      (node (ref "U3") (pin "24") (pinfunction "NC_24") (pintype "unspecified+no_connect"))
    )
    (net (code "106") (name "unconnected-(U3-OSCI-Pad27)") (class "Default")
      (node (ref "U3") (pin "27") (pinfunction "OSCI_27") (pintype "unspecified+no_connect"))
    )
    (net (code "107") (name "unconnected-(U3-OSCO-Pad28)") (class "Default")
      (node (ref "U3") (pin "28") (pinfunction "OSCO_28") (pintype "output+no_connect"))
    )
    (net (code "108") (name "unconnected-(U3-RI-Pad6)") (class "Default")
      (node (ref "U3") (pin "6") (pinfunction "RI_6") (pintype "unspecified+no_connect"))
    )
    (net (code "109") (name "unconnected-(U3-RTS-Pad3)") (class "Default")
      (node (ref "U3") (pin "3") (pinfunction "RTS_3") (pintype "output+no_connect"))
    )
    (net (code "110") (name "unconnected-(U3-TEST-Pad26)") (class "Default")
      (node (ref "U3") (pin "26") (pinfunction "TEST_26") (pintype "unspecified+no_connect"))
    )
    (net (code "111") (name "unconnected-(U4-CSB-Pad1)") (class "Default")
      (node (ref "U4") (pin "1") (pinfunction "CSB_1") (pintype "unspecified+no_connect"))
    )
    (net (code "112") (name "unconnected-(U4-SDO-Pad4)") (class "Default")
      (node (ref "U4") (pin "4") (pinfunction "SDO_4") (pintype "unspecified+no_connect"))
    )
    (net (code "113") (name "unconnected-(U6-BP-Pad4)") (class "Default")
      (node (ref "U6") (pin "4") (pinfunction "BP_4") (pintype "input+no_connect"))
    )
    (net (code "114") (name "unconnected-(USB2-ID-Pad4)") (class "Default")
      (node (ref "USB2") (pin "4") (pinfunction "ID_4") (pintype "input+no_connect"))
    )
    (net (code "115") (name "unconnected-(V-Pad2)") (class "Default")
      (node (ref "V") (pin "2") (pinfunction "2_2") (pintype "input+no_connect"))
    )
    (net (code "116") (name "unconnected-(V-Pad3)") (class "Default")
      (node (ref "V") (pin "3") (pinfunction "3_3") (pintype "input+no_connect"))
    )
    (net (code "117") (name "unconnected-(V-Pad4)") (class "Default")
      (node (ref "V") (pin "4") (pinfunction "4_4") (pintype "input+no_connect"))
    )
    (net (code "118") (name "unconnected-(V-Pad5)") (class "Default")
      (node (ref "V") (pin "5") (pinfunction "5_5") (pintype "input+no_connect"))
    )
    (net (code "119") (name "unconnected-(V-Pad6)") (class "Default")
      (node (ref "V") (pin "6") (pinfunction "6_6") (pintype "input+no_connect"))
    )
  )
)
